# Buttons.net
KiCad netlist of a schematic drawn in Altium Designer
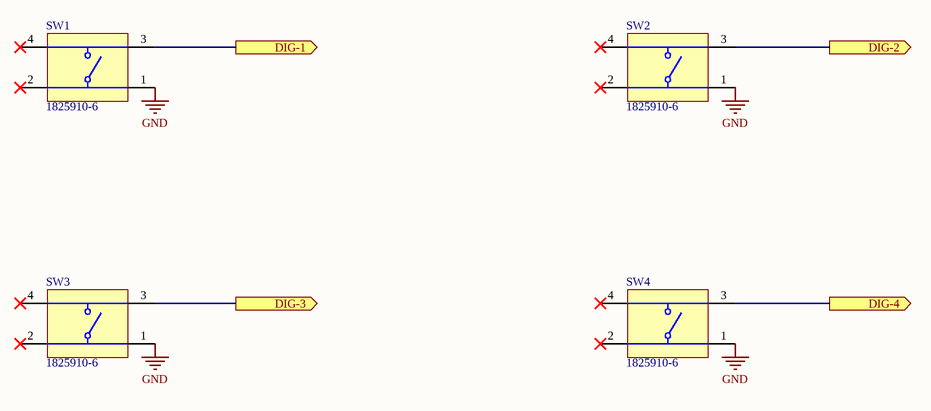
[diagram p0: Buttons.SchDoc]

(export (version "E")
  (design (tool "Eeschema 10.0.6"))
  (components
    (comp (ref "SW1")
      (value "1825910-6")
      (footprint "TECO-1825910-6_V")
      (description "Tact Switch, SPST-NO, 0.05 A, -35 to 85 degC, 4-Pin THD, RoHS, Bulk")
      (fields (field (name "MANUFACTURER") "TE Connectivity"))
      (libsource (lib "Altium Content Vault") (part "SW-SPST-4_A"))
    )
    (comp (ref "SW2")
      (value "1825910-6")
      (footprint "TECO-1825910-6_V")
      (description "Tact Switch, SPST-NO, 0.05 A, -35 to 85 degC, 4-Pin THD, RoHS, Bulk")
      (fields (field (name "MANUFACTURER") "TE Connectivity"))
      (libsource (lib "Altium Content Vault") (part "SW-SPST-4_A"))
    )
    (comp (ref "SW3")
      (value "1825910-6")
      (footprint "TECO-1825910-6_V")
      (description "Tact Switch, SPST-NO, 0.05 A, -35 to 85 degC, 4-Pin THD, RoHS, Bulk")
      (fields (field (name "MANUFACTURER") "TE Connectivity"))
      (libsource (lib "Altium Content Vault") (part "SW-SPST-4_A"))
    )
    (comp (ref "SW4")
      (value "1825910-6")
      (footprint "TECO-1825910-6_V")
      (description "Tact Switch, SPST-NO, 0.05 A, -35 to 85 degC, 4-Pin THD, RoHS, Bulk")
      (fields (field (name "MANUFACTURER") "TE Connectivity"))
      (libsource (lib "Altium Content Vault") (part "SW-SPST-4_A"))
    )
  )
  (nets
    (net (code "1") (name "/DIG-1") (class "Default")
      (node (ref "SW1") (pin "3") (pinfunction "3_3") (pintype "passive"))
    )
    (net (code "2") (name "/DIG-2") (class "Default")
      (node (ref "SW2") (pin "3") (pinfunction "3_3") (pintype "passive"))
    )
    (net (code "3") (name "/DIG-3") (class "Default")
      (node (ref "SW3") (pin "3") (pinfunction "3_3") (pintype "passive"))
    )
    (net (code "4") (name "/DIG-4") (class "Default")
      (node (ref "SW4") (pin "3") (pinfunction "3_3") (pintype "passive"))
    )
    (net (code "5") (name "GND") (class "Default")
      (node (ref "SW1") (pin "1") (pinfunction "1_1") (pintype "passive"))
      (node (ref "SW2") (pin "1") (pinfunction "1_1") (pintype "passive"))
      (node (ref "SW3") (pin "1") (pinfunction "1_1") (pintype "passive"))
      (node (ref "SW4") (pin "1") (pinfunction "1_1") (pintype "passive"))
    )
    (net (code "6") (name "unconnected-(SW1-Pad2)") (class "Default")
      (node (ref "SW1") (pin "2") (pinfunction "2_2") (pintype "passive+no_connect"))
    )
    (net (code "7") (name "unconnected-(SW1-Pad4)") (class "Default")
      (node (ref "SW1") (pin "4") (pinfunction "4_4") (pintype "passive+no_connect"))
    )
    (net (code "8") (name "unconnected-(SW2-Pad2)") (class "Default")
      (node (ref "SW2") (pin "2") (pinfunction "2_2") (pintype "passive+no_connect"))
    )
    (net (code "9") (name "unconnected-(SW2-Pad4)") (class "Default")
      (node (ref "SW2") (pin "4") (pinfunction "4_4") (pintype "passive+no_connect"))
    )
    (net (code "10") (name "unconnected-(SW3-Pad2)") (class "Default")
      (node (ref "SW3") (pin "2") (pinfunction "2_2") (pintype "passive+no_connect"))
    )
    (net (code "11") (name "unconnected-(SW3-Pad4)") (class "Default")
      (node (ref "SW3") (pin "4") (pinfunction "4_4") (pintype "passive+no_connect"))
    )
    (net (code "12") (name "unconnected-(SW4-Pad2)") (class "Default")
      (node (ref "SW4") (pin "2") (pinfunction "2_2") (pintype "passive+no_connect"))
    )
    (net (code "13") (name "unconnected-(SW4-Pad4)") (class "Default")
      (node (ref "SW4") (pin "4") (pinfunction "4_4") (pintype "passive+no_connect"))
    )
  )
)
